# 10-DPLL-1.net
KiCad netlist of a schematic drawn in Altium Designer
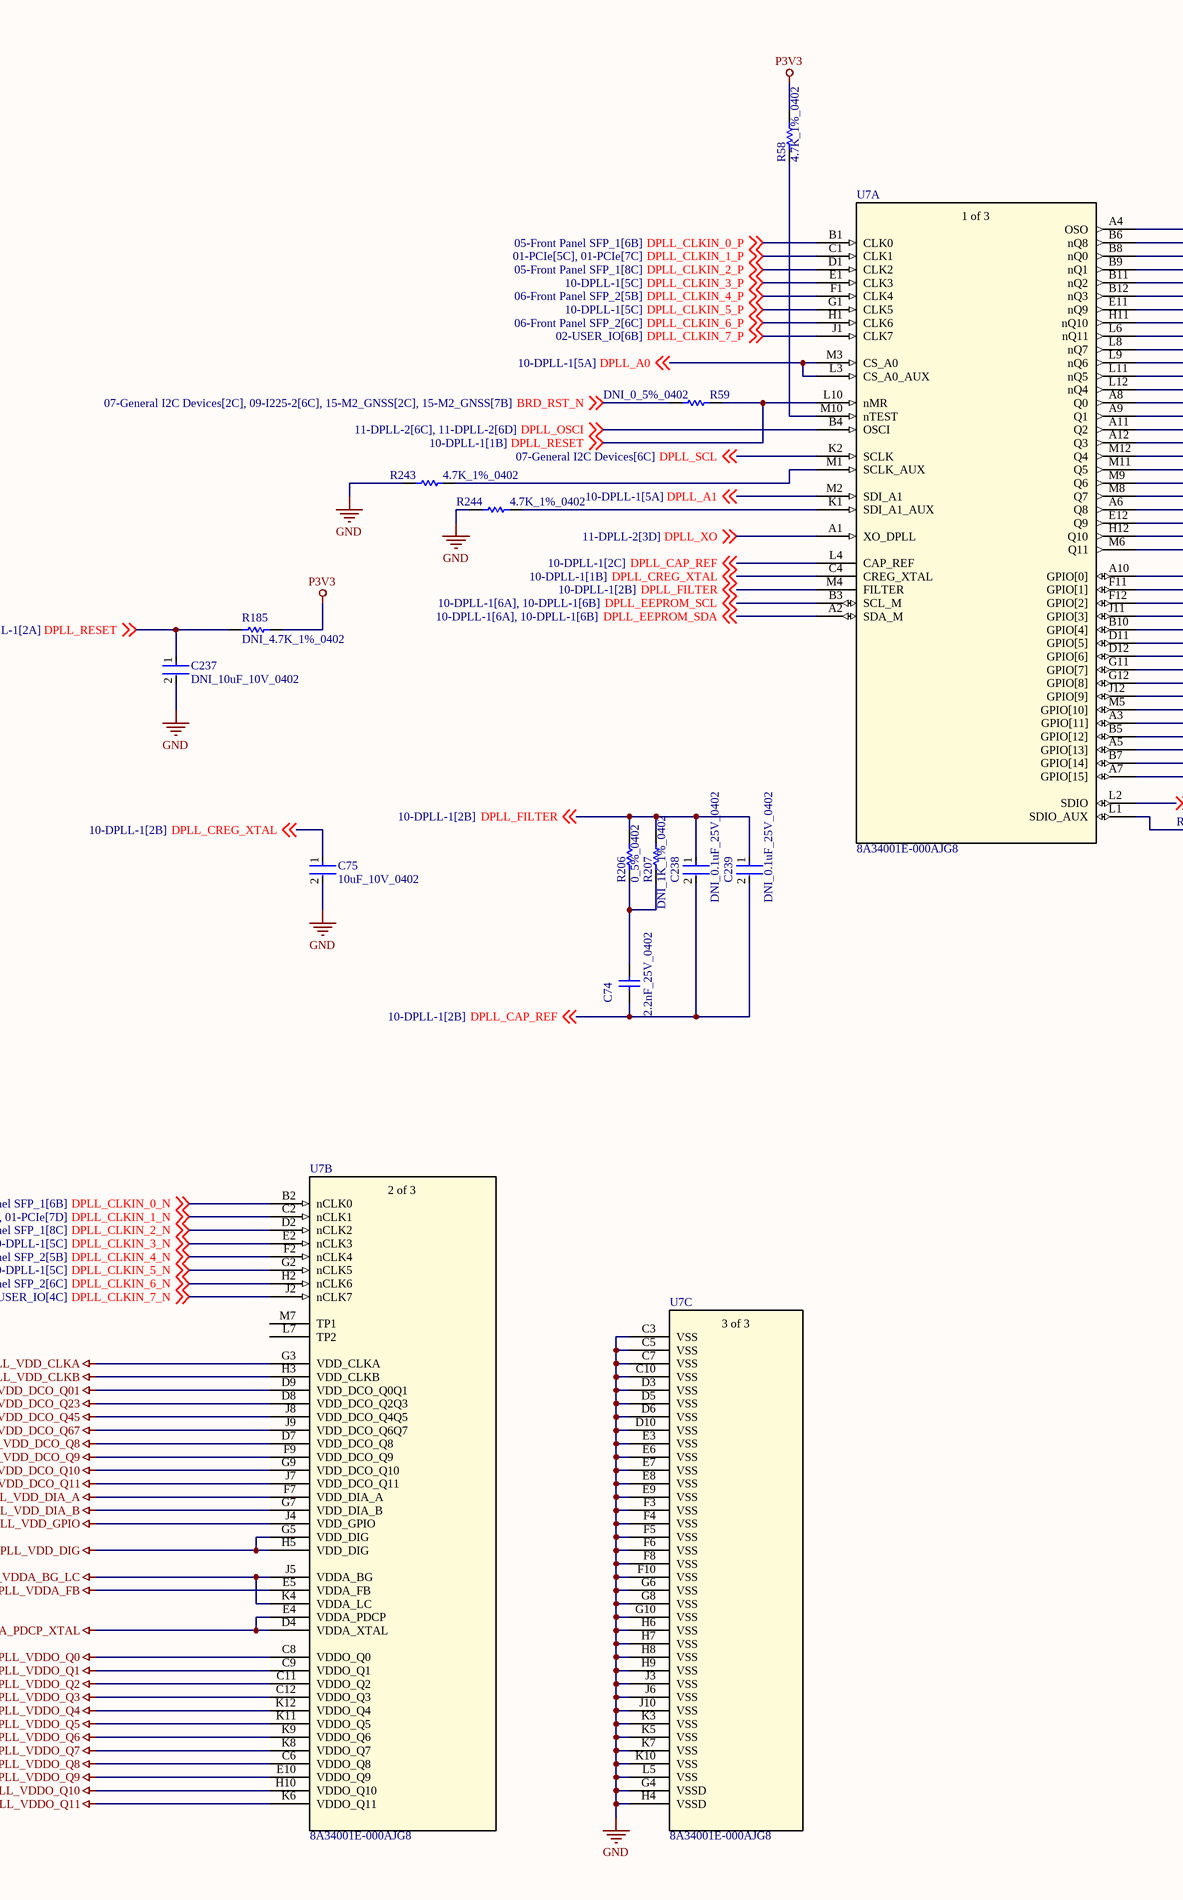
[diagram p0: 10-DPLL-1.SchDoc, left]
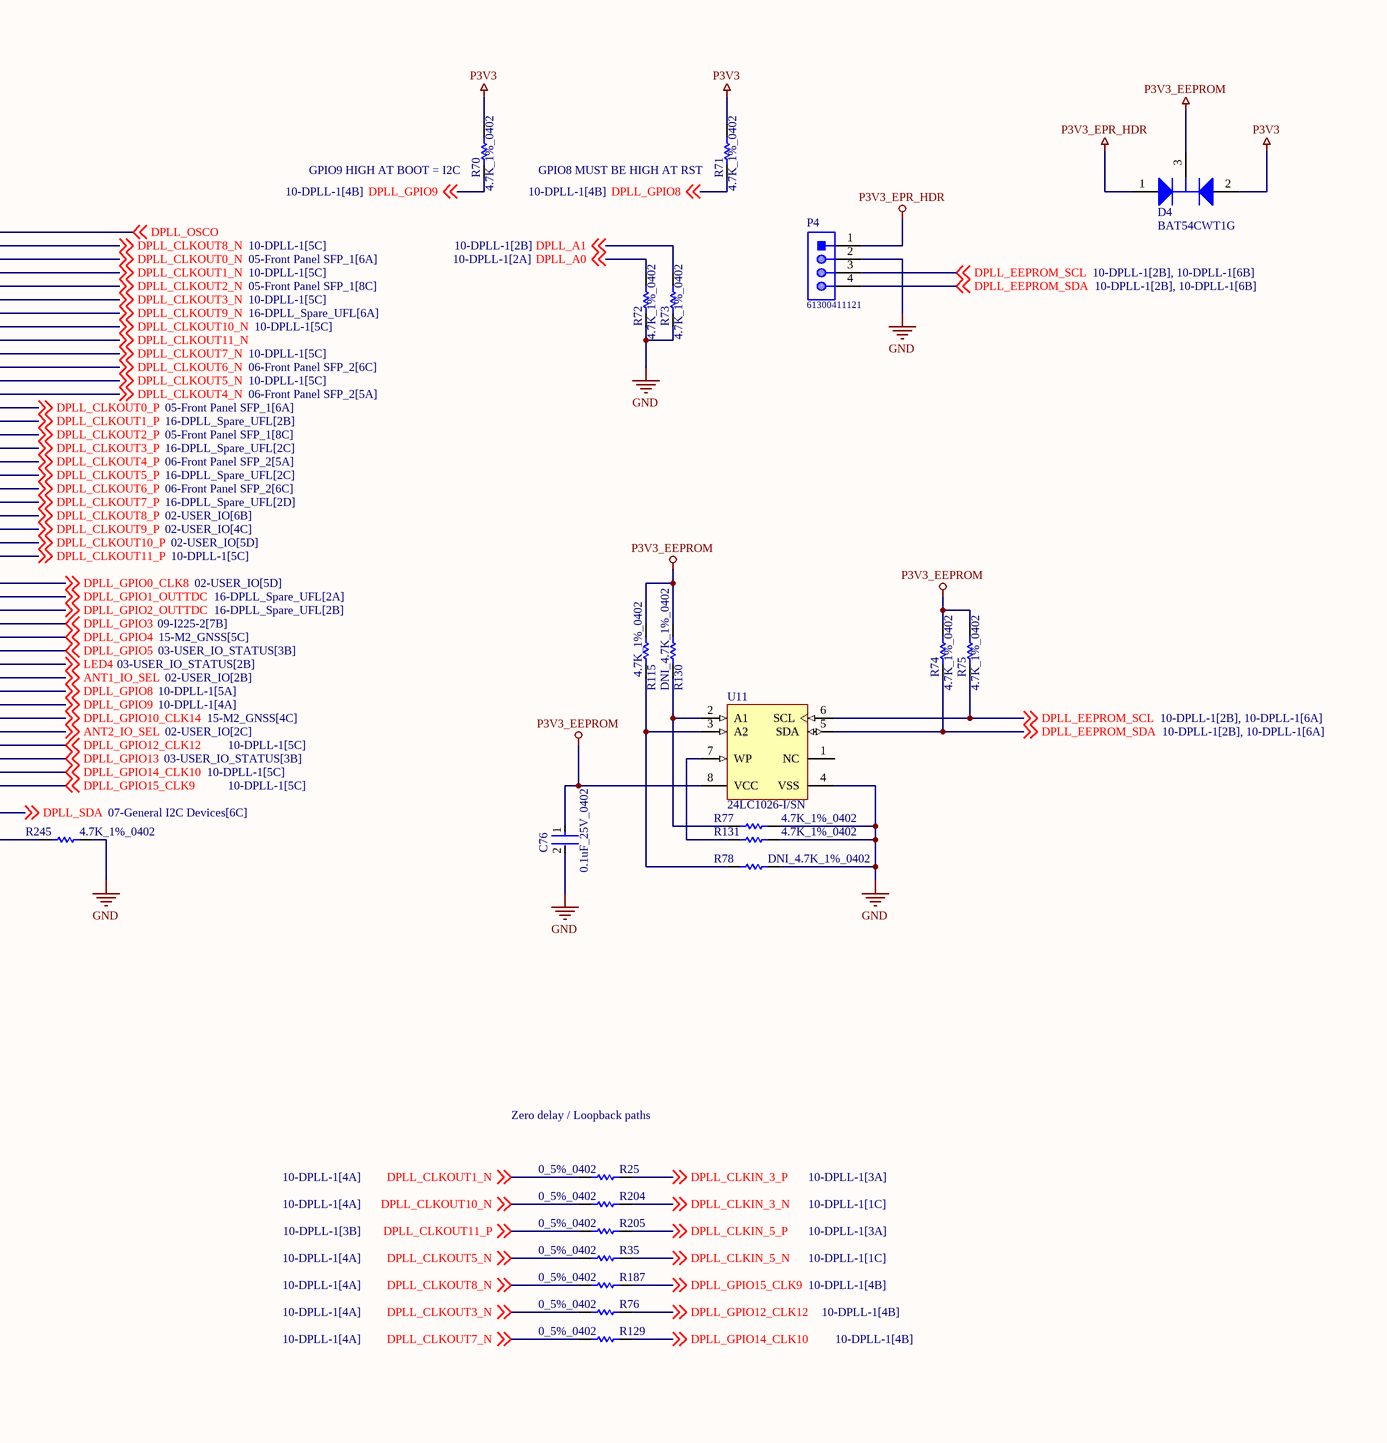
[diagram p1: 10-DPLL-1.SchDoc, right]

(export (version "E")
  (design (tool "Eeschema 10.0.6"))
  (components
    (comp (ref "C74")
      (value "2.2nF_25V_0402")
      (footprint "CAPC1005X56X25LL10T15")
      (fields
        (field (name "MANUFACTURER") "AVX Interconnect / Elco")
        (field (name "PART NUMBER") "04025C222JAT2A")
      )
      (libsource (lib "Altium Content Vault") (part "CAP"))
    )
    (comp (ref "C75")
      (value "10uF_10V_0402")
      (footprint "FP-CL05A106MP5NUNC-MFG")
      (description "CAP CER 10UF 10V X5R 0402")
      (fields
        (field (name "OCTOPART") "https://octopart.com/cl05a106mp5nunc-samsung-22457395")
        (field (name "TOLERANCE") "20%")
      )
      (libsource (lib "Altium Content Vault") (part "b4654b650e69147ec39a6b967a45e02"))
    )
    (comp (ref "C76")
      (value "0.1uF_25V_0402")
      (footprint "FP-0402-L_1_0_1-W_0_5_0_1-IPC_C")
      (description "General Purpose Ceramic Capacitor, 0402, 100nF, 10%, X7R, 15%, 25V")
      (fields (field (name "VOLTAGE") "25V") (field (name "TOLERANCE") "10%"))
      (libsource (lib "Altium Content Vault") (part "b4654b650e69147ec39a6b967a45e02"))
    )
    (comp (ref "C237")
      (value "DNI_10uF_10V_0402")
      (footprint "FP-CL05A106MP5NUNC-MFG")
      (description "CAP CER 10UF 10V X5R 0402")
      (fields
        (field (name "OCTOPART") "https://octopart.com/cl05a106mp5nunc-samsung-22457395")
        (field (name "TOLERANCE") "20%")
      )
      (libsource (lib "Altium Content Vault") (part "b4654b650e69147ec39a6b967a45e02"))
    )
    (comp (ref "C238")
      (value "DNI_0.1uF_25V_0402")
      (footprint "FP-0402-L_1_0_1-W_0_5_0_1-IPC_C")
      (description "General Purpose Ceramic Capacitor, 0402, 100nF, 10%, X7R, 15%, 25V")
      (fields (field (name "VOLTAGE") "25V") (field (name "TOLERANCE") "10%"))
      (libsource (lib "Altium Content Vault") (part "b4654b650e69147ec39a6b967a45e02"))
    )
    (comp (ref "C239")
      (value "DNI_0.1uF_25V_0402")
      (footprint "FP-0402-L_1_0_1-W_0_5_0_1-IPC_C")
      (description "General Purpose Ceramic Capacitor, 0402, 100nF, 10%, X7R, 15%, 25V")
      (fields (field (name "VOLTAGE") "25V") (field (name "TOLERANCE") "10%"))
      (libsource (lib "Altium Content Vault") (part "b4654b650e69147ec39a6b967a45e02"))
    )
    (comp (ref "D4")
      (value "BAT54CWT1G")
      (footprint "ONSC-SOT-323-3-419-04_V")
      (description "Dual Series Cathode Schottky Barrier Diodes, 3-Pin SOT-323, Pb-Free, Tape and Reel")
      (fields (field (name "MANUFACTURER") "On Semiconductor"))
      (libsource (lib "Altium Content Vault") (part "ONSC-D-A1A2K3-3"))
    )
    (comp (ref "P4")
      (value "61300411121")
      (footprint "61300411121")
      (description "THT Vertical Pin Header WR-PHD, Pitch 2.54 mm, Single Row, 4 pins")
      (fields (field (name "MANUFACTURER") "Wurth Elektronik") (field (name "PUBLISHER") "WurthElektronik"))
      (libsource (lib "Altium Content Vault") (part "WE-CN-1P-M-R4"))
    )
    (comp (ref "R25")
      (value "0_5%_0402")
      (footprint "RESC1005X40X25LL10T10")
      (fields (field (name "MANUFACTURER") "KOA Speer") (field (name "PART NUMBER") "RK73Z1ETTP"))
      (libsource (lib "Altium Content Vault") (part "RES"))
    )
    (comp (ref "R35")
      (value "0_5%_0402")
      (footprint "RESC1005X40X25LL10T10")
      (fields (field (name "MANUFACTURER") "KOA Speer") (field (name "PART NUMBER") "RK73Z1ETTP"))
      (libsource (lib "Altium Content Vault") (part "RES"))
    )
    (comp (ref "R58")
      (value "4.7K_1%_0402")
      (footprint "RESC1005X40X25NL10T10")
      (fields (field (name "MANUFACTURER") "Bourns") (field (name "PART NUMBER") "CR0402-FX-4701GLF"))
      (libsource (lib "Altium Content Vault") (part "RES"))
    )
    (comp (ref "R59")
      (value "DNI_0_5%_0402")
      (footprint "RESC1005X40X25LL10T10")
      (fields (field (name "MANUFACTURER") "KOA Speer") (field (name "PART NUMBER") "RK73Z1ETTP"))
      (libsource (lib "Altium Content Vault") (part "RES"))
    )
    (comp (ref "R70")
      (value "4.7K_1%_0402")
      (footprint "RESC1005X40X25NL10T10")
      (fields (field (name "MANUFACTURER") "Bourns") (field (name "PART NUMBER") "CR0402-FX-4701GLF"))
      (libsource (lib "Altium Content Vault") (part "RES"))
    )
    (comp (ref "R71")
      (value "4.7K_1%_0402")
      (footprint "RESC1005X40X25NL10T10")
      (fields (field (name "MANUFACTURER") "Bourns") (field (name "PART NUMBER") "CR0402-FX-4701GLF"))
      (libsource (lib "Altium Content Vault") (part "RES"))
    )
    (comp (ref "R72")
      (value "4.7K_1%_0402")
      (footprint "RESC1005X40X25NL10T10")
      (fields (field (name "MANUFACTURER") "Bourns") (field (name "PART NUMBER") "CR0402-FX-4701GLF"))
      (libsource (lib "Altium Content Vault") (part "RES"))
    )
    (comp (ref "R73")
      (value "4.7K_1%_0402")
      (footprint "RESC1005X40X25NL10T10")
      (fields (field (name "MANUFACTURER") "Bourns") (field (name "PART NUMBER") "CR0402-FX-4701GLF"))
      (libsource (lib "Altium Content Vault") (part "RES"))
    )
    (comp (ref "R74")
      (value "4.7K_1%_0402")
      (footprint "RESC1005X40X25NL10T10")
      (fields (field (name "MANUFACTURER") "Bourns") (field (name "PART NUMBER") "CR0402-FX-4701GLF"))
      (libsource (lib "Altium Content Vault") (part "RES"))
    )
    (comp (ref "R75")
      (value "4.7K_1%_0402")
      (footprint "RESC1005X40X25NL10T10")
      (fields (field (name "MANUFACTURER") "Bourns") (field (name "PART NUMBER") "CR0402-FX-4701GLF"))
      (libsource (lib "Altium Content Vault") (part "RES"))
    )
    (comp (ref "R76")
      (value "0_5%_0402")
      (footprint "RESC1005X40X25LL10T10")
      (fields (field (name "MANUFACTURER") "KOA Speer") (field (name "PART NUMBER") "RK73Z1ETTP"))
      (libsource (lib "Altium Content Vault") (part "RES"))
    )
    (comp (ref "R77")
      (value "4.7K_1%_0402")
      (footprint "RESC1005X40X25NL10T10")
      (fields (field (name "MANUFACTURER") "Bourns") (field (name "PART NUMBER") "CR0402-FX-4701GLF"))
      (libsource (lib "Altium Content Vault") (part "RES"))
    )
    (comp (ref "R78")
      (value "DNI_4.7K_1%_0402")
      (footprint "RESC1005X40X25NL10T10")
      (fields (field (name "MANUFACTURER") "Bourns") (field (name "PART NUMBER") "CR0402-FX-4701GLF"))
      (libsource (lib "Altium Content Vault") (part "RES"))
    )
    (comp (ref "R115")
      (value "4.7K_1%_0402")
      (footprint "RESC1005X40X25NL10T10")
      (fields (field (name "MANUFACTURER") "Bourns") (field (name "PART NUMBER") "CR0402-FX-4701GLF"))
      (libsource (lib "Altium Content Vault") (part "RES"))
    )
    (comp (ref "R129")
      (value "0_5%_0402")
      (footprint "RESC1005X40X25LL10T10")
      (fields (field (name "MANUFACTURER") "KOA Speer") (field (name "PART NUMBER") "RK73Z1ETTP"))
      (libsource (lib "Altium Content Vault") (part "RES"))
    )
    (comp (ref "R130")
      (value "DNI_4.7K_1%_0402")
      (footprint "RESC1005X40X25NL10T10")
      (fields (field (name "MANUFACTURER") "Bourns") (field (name "PART NUMBER") "CR0402-FX-4701GLF"))
      (libsource (lib "Altium Content Vault") (part "RES"))
    )
    (comp (ref "R131")
      (value "4.7K_1%_0402")
      (footprint "RESC1005X40X25NL10T10")
      (fields (field (name "MANUFACTURER") "Bourns") (field (name "PART NUMBER") "CR0402-FX-4701GLF"))
      (libsource (lib "Altium Content Vault") (part "RES"))
    )
    (comp (ref "R185")
      (value "DNI_4.7K_1%_0402")
      (footprint "RESC1005X40X25NL10T10")
      (fields (field (name "MANUFACTURER") "Bourns") (field (name "PART NUMBER") "CR0402-FX-4701GLF"))
      (libsource (lib "Altium Content Vault") (part "RES"))
    )
    (comp (ref "R187")
      (value "0_5%_0402")
      (footprint "RESC1005X40X25LL10T10")
      (fields (field (name "MANUFACTURER") "KOA Speer") (field (name "PART NUMBER") "RK73Z1ETTP"))
      (libsource (lib "Altium Content Vault") (part "RES"))
    )
    (comp (ref "R204")
      (value "0_5%_0402")
      (footprint "RESC1005X40X25LL10T10")
      (fields (field (name "MANUFACTURER") "KOA Speer") (field (name "PART NUMBER") "RK73Z1ETTP"))
      (libsource (lib "Altium Content Vault") (part "RES"))
    )
    (comp (ref "R205")
      (value "0_5%_0402")
      (footprint "RESC1005X40X25LL10T10")
      (fields (field (name "MANUFACTURER") "KOA Speer") (field (name "PART NUMBER") "RK73Z1ETTP"))
      (libsource (lib "Altium Content Vault") (part "RES"))
    )
    (comp (ref "R206")
      (value "0_5%_0402")
      (footprint "RESC1005X40X25LL10T10")
      (fields (field (name "MANUFACTURER") "KOA Speer") (field (name "PART NUMBER") "RK73Z1ETTP"))
      (libsource (lib "Altium Content Vault") (part "RES"))
    )
    (comp (ref "R207")
      (value "DNI_1K_1%_0402")
      (footprint "RESC1005X40X25NL05T05")
      (fields (field (name "MANUFACTURER") "Vishay Dale") (field (name "PART NUMBER") "CRCW04021K00FKTD"))
      (libsource (lib "Altium Content Vault") (part "RES"))
    )
    (comp (ref "R243")
      (value "4.7K_1%_0402")
      (footprint "RESC1005X40X25NL10T10")
      (fields (field (name "MANUFACTURER") "Bourns") (field (name "PART NUMBER") "CR0402-FX-4701GLF"))
      (libsource (lib "Altium Content Vault") (part "RES"))
    )
    (comp (ref "R244")
      (value "4.7K_1%_0402")
      (footprint "RESC1005X40X25NL10T10")
      (fields (field (name "MANUFACTURER") "Bourns") (field (name "PART NUMBER") "CR0402-FX-4701GLF"))
      (libsource (lib "Altium Content Vault") (part "RES"))
    )
    (comp (ref "R245")
      (value "4.7K_1%_0402")
      (footprint "RESC1005X40X25NL10T10")
      (fields (field (name "MANUFACTURER") "Bourns") (field (name "PART NUMBER") "CR0402-FX-4701GLF"))
      (libsource (lib "Altium Content Vault") (part "RES"))
    )
    (comp (ref "U7")
      (value "8A34001E-000AJG8")
      (footprint "144-CABGA_REN")
      (description "No Description Available")
      (fields (field (name "COPYRIGHT") "Copyright (C) 2024 Ultra Librarian. All rights reserved."))
      (libsource (lib "8A34001E-000AJG8") (part "8A34001E-000AJG8"))
    )
    (comp (ref "U11")
      (value "24LC1026-I/SN")
      (footprint "MCHP-SOIC-SN8_N")
      (description "1024K bits I2C™ Serial EEPROM, 2.5 to 5.5 V, 400 kHz, -40 to 85 degC, 8-pin SOIC (SN8), Tube")
      (fields (field (name "MANUFACTURER") "Microchip"))
      (libsource (lib "Altium Content Vault") (part "MCHP-24LC1026-SOIC-8"))
    )
  )
  (nets
    (net (code "1") (name "ANT1_IO_SEL") (class "Default")
      (node (ref "U7") (pin "G11") (pinfunction "GPIO[7]_G11") (pintype "bidirectional"))
    )
    (net (code "2") (name "ANT2_IO_SEL") (class "Default")
      (node (ref "U7") (pin "A3") (pinfunction "GPIO[11]_A3") (pintype "bidirectional"))
    )
    (net (code "3") (name "BRD_RST_N") (class "Default")
      (node (ref "R59") (pin "1") (pinfunction "1_1") (pintype "passive"))
    )
    (net (code "4") (name "DPLL_A0") (class "Default")
      (node (ref "R72") (pin "1") (pinfunction "1_1") (pintype "passive"))
      (node (ref "U7") (pin "L3") (pinfunction "CS_A0_AUX_L3") (pintype "input"))
      (node (ref "U7") (pin "M3") (pinfunction "CS_A0_M3") (pintype "input"))
    )
    (net (code "5") (name "DPLL_A1") (class "Default")
      (node (ref "R73") (pin "1") (pinfunction "1_1") (pintype "passive"))
      (node (ref "U7") (pin "M2") (pinfunction "SDI_A1_M2") (pintype "input"))
    )
    (net (code "6") (name "DPLL_CAP_REF") (class "Default")
      (node (ref "C238") (pin "2") (pinfunction "2_2") (pintype "passive"))
      (node (ref "C239") (pin "2") (pinfunction "2_2") (pintype "passive"))
      (node (ref "C74") (pin "1") (pinfunction "1_1") (pintype "passive"))
      (node (ref "U7") (pin "L4") (pinfunction "CAP_REF_L4") (pintype "passive"))
    )
    (net (code "7") (name "DPLL_CLKIN_0_N") (class "Default")
      (node (ref "U7") (pin "B2") (pinfunction "nCLK0_B2") (pintype "input"))
    )
    (net (code "8") (name "DPLL_CLKIN_0_P") (class "Default")
      (node (ref "U7") (pin "B1") (pinfunction "CLK0_B1") (pintype "input"))
    )
    (net (code "9") (name "DPLL_CLKIN_1_N") (class "Default")
      (node (ref "U7") (pin "C2") (pinfunction "nCLK1_C2") (pintype "input"))
    )
    (net (code "10") (name "DPLL_CLKIN_1_P") (class "Default")
      (node (ref "U7") (pin "C1") (pinfunction "CLK1_C1") (pintype "input"))
    )
    (net (code "11") (name "DPLL_CLKIN_2_N") (class "Default")
      (node (ref "U7") (pin "D2") (pinfunction "nCLK2_D2") (pintype "input"))
    )
    (net (code "12") (name "DPLL_CLKIN_2_P") (class "Default")
      (node (ref "U7") (pin "D1") (pinfunction "CLK2_D1") (pintype "input"))
    )
    (net (code "13") (name "DPLL_CLKIN_3_N") (class "Default")
      (node (ref "R204") (pin "2") (pinfunction "2_2") (pintype "passive"))
      (node (ref "U7") (pin "E2") (pinfunction "nCLK3_E2") (pintype "input"))
    )
    (net (code "14") (name "DPLL_CLKIN_3_P") (class "Default")
      (node (ref "R25") (pin "2") (pinfunction "2_2") (pintype "passive"))
      (node (ref "U7") (pin "E1") (pinfunction "CLK3_E1") (pintype "input"))
    )
    (net (code "15") (name "DPLL_CLKIN_4_N") (class "Default")
      (node (ref "U7") (pin "F2") (pinfunction "nCLK4_F2") (pintype "input"))
    )
    (net (code "16") (name "DPLL_CLKIN_4_P") (class "Default")
      (node (ref "U7") (pin "F1") (pinfunction "CLK4_F1") (pintype "input"))
    )
    (net (code "17") (name "DPLL_CLKIN_5_N") (class "Default")
      (node (ref "R35") (pin "2") (pinfunction "2_2") (pintype "passive"))
      (node (ref "U7") (pin "G2") (pinfunction "nCLK5_G2") (pintype "input"))
    )
    (net (code "18") (name "DPLL_CLKIN_5_P") (class "Default")
      (node (ref "R205") (pin "2") (pinfunction "2_2") (pintype "passive"))
      (node (ref "U7") (pin "G1") (pinfunction "CLK5_G1") (pintype "input"))
    )
    (net (code "19") (name "DPLL_CLKIN_6_N") (class "Default")
      (node (ref "U7") (pin "H2") (pinfunction "nCLK6_H2") (pintype "input"))
    )
    (net (code "20") (name "DPLL_CLKIN_6_P") (class "Default")
      (node (ref "U7") (pin "H1") (pinfunction "CLK6_H1") (pintype "input"))
    )
    (net (code "21") (name "DPLL_CLKIN_7_N") (class "Default")
      (node (ref "U7") (pin "J2") (pinfunction "nCLK7_J2") (pintype "input"))
    )
    (net (code "22") (name "DPLL_CLKIN_7_P") (class "Default")
      (node (ref "U7") (pin "J1") (pinfunction "CLK7_J1") (pintype "input"))
    )
    (net (code "23") (name "DPLL_CLKOUT0_N") (class "Default")
      (node (ref "U7") (pin "B8") (pinfunction "nQ0_B8") (pintype "output"))
    )
    (net (code "24") (name "DPLL_CLKOUT0_P") (class "Default")
      (node (ref "U7") (pin "A8") (pinfunction "Q0_A8") (pintype "output"))
    )
    (net (code "25") (name "DPLL_CLKOUT1_N") (class "Default")
      (node (ref "R25") (pin "1") (pinfunction "1_1") (pintype "passive"))
      (node (ref "U7") (pin "B9") (pinfunction "nQ1_B9") (pintype "output"))
    )
    (net (code "26") (name "DPLL_CLKOUT1_P") (class "Default")
      (node (ref "U7") (pin "A9") (pinfunction "Q1_A9") (pintype "output"))
    )
    (net (code "27") (name "DPLL_CLKOUT2_N") (class "Default")
      (node (ref "U7") (pin "B11") (pinfunction "nQ2_B11") (pintype "output"))
    )
    (net (code "28") (name "DPLL_CLKOUT2_P") (class "Default")
      (node (ref "U7") (pin "A11") (pinfunction "Q2_A11") (pintype "output"))
    )
    (net (code "29") (name "DPLL_CLKOUT3_N") (class "Default")
      (node (ref "R76") (pin "1") (pinfunction "1_1") (pintype "passive"))
      (node (ref "U7") (pin "B12") (pinfunction "nQ3_B12") (pintype "output"))
    )
    (net (code "30") (name "DPLL_CLKOUT3_P") (class "Default")
      (node (ref "U7") (pin "A12") (pinfunction "Q3_A12") (pintype "output"))
    )
    (net (code "31") (name "DPLL_CLKOUT4_N") (class "Default")
      (node (ref "U7") (pin "L12") (pinfunction "nQ4_L12") (pintype "output"))
    )
    (net (code "32") (name "DPLL_CLKOUT4_P") (class "Default")
      (node (ref "U7") (pin "M12") (pinfunction "Q4_M12") (pintype "output"))
    )
    (net (code "33") (name "DPLL_CLKOUT5_N") (class "Default")
      (node (ref "R35") (pin "1") (pinfunction "1_1") (pintype "passive"))
      (node (ref "U7") (pin "L11") (pinfunction "nQ5_L11") (pintype "output"))
    )
    (net (code "34") (name "DPLL_CLKOUT5_P") (class "Default")
      (node (ref "U7") (pin "M11") (pinfunction "Q5_M11") (pintype "output"))
    )
    (net (code "35") (name "DPLL_CLKOUT6_N") (class "Default")
      (node (ref "U7") (pin "L9") (pinfunction "nQ6_L9") (pintype "output"))
    )
    (net (code "36") (name "DPLL_CLKOUT6_P") (class "Default")
      (node (ref "U7") (pin "M9") (pinfunction "Q6_M9") (pintype "output"))
    )
    (net (code "37") (name "DPLL_CLKOUT7_N") (class "Default")
      (node (ref "R129") (pin "1") (pinfunction "1_1") (pintype "passive"))
      (node (ref "U7") (pin "L8") (pinfunction "nQ7_L8") (pintype "output"))
    )
    (net (code "38") (name "DPLL_CLKOUT7_P") (class "Default")
      (node (ref "U7") (pin "M8") (pinfunction "Q7_M8") (pintype "output"))
    )
    (net (code "39") (name "DPLL_CLKOUT8_N") (class "Default")
      (node (ref "R187") (pin "1") (pinfunction "1_1") (pintype "passive"))
      (node (ref "U7") (pin "B6") (pinfunction "nQ8_B6") (pintype "output"))
    )
    (net (code "40") (name "DPLL_CLKOUT8_P") (class "Default")
      (node (ref "U7") (pin "A6") (pinfunction "Q8_A6") (pintype "output"))
    )
    (net (code "41") (name "DPLL_CLKOUT9_N") (class "Default")
      (node (ref "U7") (pin "E11") (pinfunction "nQ9_E11") (pintype "output"))
    )
    (net (code "42") (name "DPLL_CLKOUT9_P") (class "Default")
      (node (ref "U7") (pin "E12") (pinfunction "Q9_E12") (pintype "output"))
    )
    (net (code "43") (name "DPLL_CLKOUT10_N") (class "Default")
      (node (ref "R204") (pin "1") (pinfunction "1_1") (pintype "passive"))
      (node (ref "U7") (pin "H11") (pinfunction "nQ10_H11") (pintype "output"))
    )
    (net (code "44") (name "DPLL_CLKOUT10_P") (class "Default")
      (node (ref "U7") (pin "H12") (pinfunction "Q10_H12") (pintype "output"))
    )
    (net (code "45") (name "DPLL_CLKOUT11_N") (class "Default")
      (node (ref "U7") (pin "L6") (pinfunction "nQ11_L6") (pintype "output"))
    )
    (net (code "46") (name "DPLL_CLKOUT11_P") (class "Default")
      (node (ref "R205") (pin "1") (pinfunction "1_1") (pintype "passive"))
      (node (ref "U7") (pin "M6") (pinfunction "Q11_M6") (pintype "output"))
    )
    (net (code "47") (name "DPLL_CREG_XTAL") (class "Default")
      (node (ref "C75") (pin "1") (pinfunction "1_1") (pintype "passive"))
      (node (ref "U7") (pin "C4") (pinfunction "CREG_XTAL_C4") (pintype "passive"))
    )
    (net (code "48") (name "DPLL_EEPROM_SCL") (class "Default")
      (node (ref "P4") (pin "3") (pinfunction "3_3") (pintype "passive"))
      (node (ref "R75") (pin "2") (pinfunction "2_2") (pintype "passive"))
      (node (ref "U11") (pin "6") (pinfunction "SCL_6") (pintype "input"))
      (node (ref "U7") (pin "B3") (pinfunction "SCL_M_B3") (pintype "bidirectional"))
    )
    (net (code "49") (name "DPLL_EEPROM_SDA") (class "Default")
      (node (ref "P4") (pin "4") (pinfunction "4_4") (pintype "passive"))
      (node (ref "R74") (pin "2") (pinfunction "2_2") (pintype "passive"))
      (node (ref "U11") (pin "5") (pinfunction "SDA_5") (pintype "bidirectional"))
      (node (ref "U7") (pin "A2") (pinfunction "SDA_M_A2") (pintype "bidirectional"))
    )
    (net (code "50") (name "DPLL_FILTER") (class "Default")
      (node (ref "C238") (pin "1") (pinfunction "1_1") (pintype "passive"))
      (node (ref "C239") (pin "1") (pinfunction "1_1") (pintype "passive"))
      (node (ref "R206") (pin "2") (pinfunction "2_2") (pintype "passive"))
      (node (ref "R207") (pin "2") (pinfunction "2_2") (pintype "passive"))
      (node (ref "U7") (pin "M4") (pinfunction "FILTER_M4") (pintype "passive"))
    )
    (net (code "51") (name "DPLL_GPIO0_CLK8") (class "Default")
      (node (ref "U7") (pin "A10") (pinfunction "GPIO[0]_A10") (pintype "bidirectional"))
    )
    (net (code "52") (name "DPLL_GPIO1_OUTTDC") (class "Default")
      (node (ref "U7") (pin "F11") (pinfunction "GPIO[1]_F11") (pintype "bidirectional"))
    )
    (net (code "53") (name "DPLL_GPIO2_OUTTDC") (class "Default")
      (node (ref "U7") (pin "F12") (pinfunction "GPIO[2]_F12") (pintype "bidirectional"))
    )
    (net (code "54") (name "DPLL_GPIO3") (class "Default")
      (node (ref "U7") (pin "J11") (pinfunction "GPIO[3]_J11") (pintype "bidirectional"))
    )
    (net (code "55") (name "DPLL_GPIO4") (class "Default")
      (node (ref "U7") (pin "B10") (pinfunction "GPIO[4]_B10") (pintype "bidirectional"))
    )
    (net (code "56") (name "DPLL_GPIO5") (class "Default")
      (node (ref "U7") (pin "D11") (pinfunction "GPIO[5]_D11") (pintype "bidirectional"))
    )
    (net (code "57") (name "DPLL_GPIO8") (class "Default")
      (node (ref "R71") (pin "2") (pinfunction "2_2") (pintype "passive"))
      (node (ref "U7") (pin "G12") (pinfunction "GPIO[8]_G12") (pintype "bidirectional"))
    )
    (net (code "58") (name "DPLL_GPIO9") (class "Default")
      (node (ref "R70") (pin "2") (pinfunction "2_2") (pintype "passive"))
      (node (ref "U7") (pin "J12") (pinfunction "GPIO[9]_J12") (pintype "bidirectional"))
    )
    (net (code "59") (name "DPLL_GPIO10_CLK14") (class "Default")
      (node (ref "U7") (pin "M5") (pinfunction "GPIO[10]_M5") (pintype "bidirectional"))
    )
    (net (code "60") (name "DPLL_GPIO12_CLK12") (class "Default")
      (node (ref "R76") (pin "2") (pinfunction "2_2") (pintype "passive"))
      (node (ref "U7") (pin "B5") (pinfunction "GPIO[12]_B5") (pintype "bidirectional"))
    )
    (net (code "61") (name "DPLL_GPIO13") (class "Default")
      (node (ref "U7") (pin "A5") (pinfunction "GPIO[13]_A5") (pintype "bidirectional"))
    )
    (net (code "62") (name "DPLL_GPIO14_CLK10") (class "Default")
      (node (ref "R129") (pin "2") (pinfunction "2_2") (pintype "passive"))
      (node (ref "U7") (pin "B7") (pinfunction "GPIO[14]_B7") (pintype "bidirectional"))
    )
    (net (code "63") (name "DPLL_GPIO15_CLK9") (class "Default")
      (node (ref "R187") (pin "2") (pinfunction "2_2") (pintype "passive"))
      (node (ref "U7") (pin "A7") (pinfunction "GPIO[15]_A7") (pintype "bidirectional"))
    )
    (net (code "64") (name "DPLL_OSCI") (class "Default")
      (node (ref "U7") (pin "B4") (pinfunction "OSCI_B4") (pintype "input"))
    )
    (net (code "65") (name "DPLL_OSCO") (class "Default")
      (node (ref "U7") (pin "A4") (pinfunction "OSO_A4") (pintype "output"))
    )
    (net (code "66") (name "DPLL_RESET") (class "Default")
      (node (ref "C237") (pin "1") (pinfunction "1_1") (pintype "passive"))
      (node (ref "R185") (pin "2") (pinfunction "2_2") (pintype "passive"))
      (node (ref "R59") (pin "2") (pinfunction "2_2") (pintype "passive"))
      (node (ref "U7") (pin "L10") (pinfunction "nMR_L10") (pintype "input"))
    )
    (net (code "67") (name "DPLL_SCL") (class "Default")
      (node (ref "U7") (pin "K2") (pinfunction "SCLK_K2") (pintype "input"))
    )
    (net (code "68") (name "DPLL_SDA") (class "Default")
      (node (ref "U7") (pin "L2") (pinfunction "SDIO_L2") (pintype "bidirectional"))
    )
    (net (code "69") (name "DPLL_VDDA_BG_LC") (class "Default")
      (node (ref "U7") (pin "J5") (pinfunction "VDDA_BG_J5") (pintype "power_in"))
      (node (ref "U7") (pin "K4") (pinfunction "VDDA_LC_K4") (pintype "power_in"))
    )
    (net (code "70") (name "DPLL_VDDA_FB") (class "Default")
      (node (ref "U7") (pin "E5") (pinfunction "VDDA_FB_E5") (pintype "power_in"))
    )
    (net (code "71") (name "DPLL_VDDA_PDCP_XTAL") (class "Default")
      (node (ref "U7") (pin "D4") (pinfunction "VDDA_XTAL_D4") (pintype "power_in"))
      (node (ref "U7") (pin "E4") (pinfunction "VDDA_PDCP_E4") (pintype "power_in"))
    )
    (net (code "72") (name "DPLL_VDDO_Q0") (class "Default")
      (node (ref "U7") (pin "C8") (pinfunction "VDDO_Q0_C8") (pintype "power_in"))
    )
    (net (code "73") (name "DPLL_VDDO_Q1") (class "Default")
      (node (ref "U7") (pin "C9") (pinfunction "VDDO_Q1_C9") (pintype "power_in"))
    )
    (net (code "74") (name "DPLL_VDDO_Q2") (class "Default")
      (node (ref "U7") (pin "C11") (pinfunction "VDDO_Q2_C11") (pintype "power_in"))
    )
    (net (code "75") (name "DPLL_VDDO_Q3") (class "Default")
      (node (ref "U7") (pin "C12") (pinfunction "VDDO_Q3_C12") (pintype "power_in"))
    )
    (net (code "76") (name "DPLL_VDDO_Q4") (class "Default")
      (node (ref "U7") (pin "K12") (pinfunction "VDDO_Q4_K12") (pintype "power_in"))
    )
    (net (code "77") (name "DPLL_VDDO_Q5") (class "Default")
      (node (ref "U7") (pin "K11") (pinfunction "VDDO_Q5_K11") (pintype "power_in"))
    )
    (net (code "78") (name "DPLL_VDDO_Q6") (class "Default")
      (node (ref "U7") (pin "K9") (pinfunction "VDDO_Q6_K9") (pintype "power_in"))
    )
    (net (code "79") (name "DPLL_VDDO_Q7") (class "Default")
      (node (ref "U7") (pin "K8") (pinfunction "VDDO_Q7_K8") (pintype "power_in"))
    )
    (net (code "80") (name "DPLL_VDDO_Q8") (class "Default")
      (node (ref "U7") (pin "C6") (pinfunction "VDDO_Q8_C6") (pintype "power_in"))
    )
    (net (code "81") (name "DPLL_VDDO_Q9") (class "Default")
      (node (ref "U7") (pin "E10") (pinfunction "VDDO_Q9_E10") (pintype "power_in"))
    )
    (net (code "82") (name "DPLL_VDDO_Q10") (class "Default")
      (node (ref "U7") (pin "H10") (pinfunction "VDDO_Q10_H10") (pintype "power_in"))
    )
    (net (code "83") (name "DPLL_VDDO_Q11") (class "Default")
      (node (ref "U7") (pin "K6") (pinfunction "VDDO_Q11_K6") (pintype "power_in"))
    )
    (net (code "84") (name "DPLL_VDD_CLKA") (class "Default")
      (node (ref "U7") (pin "G3") (pinfunction "VDD_CLKA_G3") (pintype "power_in"))
    )
    (net (code "85") (name "DPLL_VDD_CLKB") (class "Default")
      (node (ref "U7") (pin "H3") (pinfunction "VDD_CLKB_H3") (pintype "power_in"))
    )
    (net (code "86") (name "DPLL_VDD_DCO_Q01") (class "Default")
      (node (ref "U7") (pin "D9") (pinfunction "VDD_DCO_Q0Q1_D9") (pintype "power_in"))
    )
    (net (code "87") (name "DPLL_VDD_DCO_Q8") (class "Default")
      (node (ref "U7") (pin "D7") (pinfunction "VDD_DCO_Q8_D7") (pintype "power_in"))
    )
    (net (code "88") (name "DPLL_VDD_DCO_Q9") (class "Default")
      (node (ref "U7") (pin "F9") (pinfunction "VDD_DCO_Q9_F9") (pintype "power_in"))
    )
    (net (code "89") (name "DPLL_VDD_DCO_Q10") (class "Default")
      (node (ref "U7") (pin "G9") (pinfunction "VDD_DCO_Q10_G9") (pintype "power_in"))
    )
    (net (code "90") (name "DPLL_VDD_DCO_Q11") (class "Default")
      (node (ref "U7") (pin "J7") (pinfunction "VDD_DCO_Q11_J7") (pintype "power_in"))
    )
    (net (code "91") (name "DPLL_VDD_DCO_Q23") (class "Default")
      (node (ref "U7") (pin "D8") (pinfunction "VDD_DCO_Q2Q3_D8") (pintype "power_in"))
    )
    (net (code "92") (name "DPLL_VDD_DCO_Q45") (class "Default")
      (node (ref "U7") (pin "J8") (pinfunction "VDD_DCO_Q4Q5_J8") (pintype "power_in"))
    )
    (net (code "93") (name "DPLL_VDD_DCO_Q67") (class "Default")
      (node (ref "U7") (pin "J9") (pinfunction "VDD_DCO_Q6Q7_J9") (pintype "power_in"))
    )
    (net (code "94") (name "DPLL_VDD_DIA_A") (class "Default")
      (node (ref "U7") (pin "F7") (pinfunction "VDD_DIA_A_F7") (pintype "power_in"))
    )
    (net (code "95") (name "DPLL_VDD_DIA_B") (class "Default")
      (node (ref "U7") (pin "G7") (pinfunction "VDD_DIA_B_G7") (pintype "power_in"))
    )
    (net (code "96") (name "DPLL_VDD_DIG") (class "Default")
      (node (ref "U7") (pin "G5") (pinfunction "VDD_DIG_G5") (pintype "power_in"))
      (node (ref "U7") (pin "H5") (pinfunction "VDD_DIG_H5") (pintype "power_in"))
    )
    (net (code "97") (name "DPLL_VDD_GPIO") (class "Default")
      (node (ref "U7") (pin "J4") (pinfunction "VDD_GPIO_J4") (pintype "power_in"))
    )
    (net (code "98") (name "DPLL_XO") (class "Default")
      (node (ref "U7") (pin "A1") (pinfunction "XO_DPLL_A1") (pintype "input"))
    )
    (net (code "99") (name "GND") (class "Default")
      (node (ref "C237") (pin "2") (pinfunction "2_2") (pintype "passive"))
      (node (ref "C75") (pin "2") (pinfunction "2_2") (pintype "passive"))
      (node (ref "C76") (pin "2") (pinfunction "2_2") (pintype "passive"))
      (node (ref "P4") (pin "2") (pinfunction "2_2") (pintype "passive"))
      (node (ref "R131") (pin "1") (pinfunction "1_1") (pintype "passive"))
      (node (ref "R243") (pin "2") (pinfunction "2_2") (pintype "passive"))
      (node (ref "R244") (pin "2") (pinfunction "2_2") (pintype "passive"))
      (node (ref "R245") (pin "1") (pinfunction "1_1") (pintype "passive"))
      (node (ref "R72") (pin "2") (pinfunction "2_2") (pintype "passive"))
      (node (ref "R73") (pin "2") (pinfunction "2_2") (pintype "passive"))
      (node (ref "R77") (pin "1") (pinfunction "1_1") (pintype "passive"))
      (node (ref "R78") (pin "2") (pinfunction "2_2") (pintype "passive"))
      (node (ref "U11") (pin "4") (pinfunction "VSS_4") (pintype "power_in"))
      (node (ref "U7") (pin "C10") (pinfunction "VSS_C10") (pintype "power_in"))
      (node (ref "U7") (pin "C3") (pinfunction "VSS_C3") (pintype "power_in"))
      (node (ref "U7") (pin "C5") (pinfunction "VSS_C5") (pintype "power_in"))
      (node (ref "U7") (pin "C7") (pinfunction "VSS_C7") (pintype "power_in"))
      (node (ref "U7") (pin "D10") (pinfunction "VSS_D10") (pintype "power_in"))
      (node (ref "U7") (pin "D3") (pinfunction "VSS_D3") (pintype "power_in"))
      (node (ref "U7") (pin "D5") (pinfunction "VSS_D5") (pintype "power_in"))
      (node (ref "U7") (pin "D6") (pinfunction "VSS_D6") (pintype "power_in"))
      (node (ref "U7") (pin "E3") (pinfunction "VSS_E3") (pintype "power_in"))
      (node (ref "U7") (pin "E6") (pinfunction "VSS_E6") (pintype "power_in"))
      (node (ref "U7") (pin "E7") (pinfunction "VSS_E7") (pintype "power_in"))
      (node (ref "U7") (pin "E8") (pinfunction "VSS_E8") (pintype "power_in"))
      (node (ref "U7") (pin "E9") (pinfunction "VSS_E9") (pintype "power_in"))
      (node (ref "U7") (pin "F10") (pinfunction "VSS_F10") (pintype "power_in"))
      (node (ref "U7") (pin "F3") (pinfunction "VSS_F3") (pintype "power_in"))
      (node (ref "U7") (pin "F4") (pinfunction "VSS_F4") (pintype "power_in"))
      (node (ref "U7") (pin "F5") (pinfunction "VSS_F5") (pintype "power_in"))
      (node (ref "U7") (pin "F6") (pinfunction "VSS_F6") (pintype "power_in"))
      (node (ref "U7") (pin "F8") (pinfunction "VSS_F8") (pintype "power_in"))
      (node (ref "U7") (pin "G10") (pinfunction "VSS_G10") (pintype "power_in"))
      (node (ref "U7") (pin "G4") (pinfunction "VSSD_G4") (pintype "power_in"))
      (node (ref "U7") (pin "G6") (pinfunction "VSS_G6") (pintype "power_in"))
      (node (ref "U7") (pin "G8") (pinfunction "VSS_G8") (pintype "power_in"))
      (node (ref "U7") (pin "H4") (pinfunction "VSSD_H4") (pintype "power_in"))
      (node (ref "U7") (pin "H6") (pinfunction "VSS_H6") (pintype "power_in"))
      (node (ref "U7") (pin "H7") (pinfunction "VSS_H7") (pintype "power_in"))
      (node (ref "U7") (pin "H8") (pinfunction "VSS_H8") (pintype "power_in"))
      (node (ref "U7") (pin "H9") (pinfunction "VSS_H9") (pintype "power_in"))
      (node (ref "U7") (pin "J10") (pinfunction "VSS_J10") (pintype "power_in"))
      (node (ref "U7") (pin "J3") (pinfunction "VSS_J3") (pintype "power_in"))
      (node (ref "U7") (pin "J6") (pinfunction "VSS_J6") (pintype "power_in"))
      (node (ref "U7") (pin "K10") (pinfunction "VSS_K10") (pintype "power_in"))
      (node (ref "U7") (pin "K3") (pinfunction "VSS_K3") (pintype "power_in"))
      (node (ref "U7") (pin "K5") (pinfunction "VSS_K5") (pintype "power_in"))
      (node (ref "U7") (pin "K7") (pinfunction "VSS_K7") (pintype "power_in"))
      (node (ref "U7") (pin "L5") (pinfunction "VSS_L5") (pintype "power_in"))
    )
    (net (code "100") (name "LED4") (class "Default")
      (node (ref "U7") (pin "D12") (pinfunction "GPIO[6]_D12") (pintype "bidirectional"))
    )
    (net (code "101") (name "Net-(C74-Pad2)") (class "Default")
      (node (ref "C74") (pin "2") (pinfunction "2_2") (pintype "passive"))
      (node (ref "R206") (pin "1") (pinfunction "1_1") (pintype "passive"))
      (node (ref "R207") (pin "1") (pinfunction "1_1") (pintype "passive"))
    )
    (net (code "102") (name "Net-(U7A-SCLK_AUX)") (class "Default")
      (node (ref "R243") (pin "1") (pinfunction "1_1") (pintype "passive"))
      (node (ref "U7") (pin "M1") (pinfunction "SCLK_AUX_M1") (pintype "input"))
    )
    (net (code "103") (name "Net-(U7A-SDIO_AUX)") (class "Default")
      (node (ref "R245") (pin "2") (pinfunction "2_2") (pintype "passive"))
      (node (ref "U7") (pin "L1") (pinfunction "SDIO_AUX_L1") (pintype "bidirectional"))
    )
    (net (code "104") (name "Net-(U7A-SDI_A1_AUX)") (class "Default")
      (node (ref "R244") (pin "1") (pinfunction "1_1") (pintype "passive"))
      (node (ref "U7") (pin "K1") (pinfunction "SDI_A1_AUX_K1") (pintype "input"))
    )
    (net (code "105") (name "Net-(U7A-nTEST)") (class "Default")
      (node (ref "R58") (pin "1") (pinfunction "1_1") (pintype "passive"))
      (node (ref "U7") (pin "M10") (pinfunction "nTEST_M10") (pintype "input"))
    )
    (net (code "106") (name "Net-(U11-A1)") (class "Default")
      (node (ref "R130") (pin "1") (pinfunction "1_1") (pintype "passive"))
      (node (ref "R77") (pin "2") (pinfunction "2_2") (pintype "passive"))
      (node (ref "U11") (pin "2") (pinfunction "A1_2") (pintype "input"))
    )
    (net (code "107") (name "Net-(U11-A2)") (class "Default")
      (node (ref "R115") (pin "1") (pinfunction "1_1") (pintype "passive"))
      (node (ref "R78") (pin "1") (pinfunction "1_1") (pintype "passive"))
      (node (ref "U11") (pin "3") (pinfunction "A2_3") (pintype "input"))
    )
    (net (code "108") (name "Net-(U11-WP)") (class "Default")
      (node (ref "R131") (pin "2") (pinfunction "2_2") (pintype "passive"))
      (node (ref "U11") (pin "7") (pinfunction "WP_7") (pintype "input"))
    )
    (net (code "109") (name "P3V3") (class "Default")
      (node (ref "D4") (pin "2") (pinfunction "A2_2") (pintype "passive"))
      (node (ref "R185") (pin "1") (pinfunction "1_1") (pintype "passive"))
      (node (ref "R58") (pin "2") (pinfunction "2_2") (pintype "passive"))
      (node (ref "R70") (pin "1") (pinfunction "1_1") (pintype "passive"))
      (node (ref "R71") (pin "1") (pinfunction "1_1") (pintype "passive"))
    )
    (net (code "110") (name "P3V3_EEPROM") (class "Default")
      (node (ref "C76") (pin "1") (pinfunction "1_1") (pintype "passive"))
      (node (ref "D4") (pin "3") (pinfunction "K_3") (pintype "passive"))
      (node (ref "R115") (pin "2") (pinfunction "2_2") (pintype "passive"))
      (node (ref "R130") (pin "2") (pinfunction "2_2") (pintype "passive"))
      (node (ref "R74") (pin "1") (pinfunction "1_1") (pintype "passive"))
      (node (ref "R75") (pin "1") (pinfunction "1_1") (pintype "passive"))
      (node (ref "U11") (pin "8") (pinfunction "VCC_8") (pintype "power_in"))
    )
    (net (code "111") (name "P3V3_EPR_HDR") (class "Default")
      (node (ref "D4") (pin "1") (pinfunction "A1_1") (pintype "passive"))
      (node (ref "P4") (pin "1") (pinfunction "1_1") (pintype "passive"))
    )
    (net (code "112") (name "unconnected-(U7B-TP1-PadM7)") (class "Default")
      (node (ref "U7") (pin "M7") (pinfunction "TP1_M7") (pintype "passive"))
    )
    (net (code "113") (name "unconnected-(U7B-TP2-PadL7)") (class "Default")
      (node (ref "U7") (pin "L7") (pinfunction "TP2_L7") (pintype "passive"))
    )
    (net (code "114") (name "unconnected-(U11-NC-Pad1)") (class "Default")
      (node (ref "U11") (pin "1") (pinfunction "NC_1") (pintype "passive"))
    )
  )
)
